# CircleValve.net
KiCad netlist of a schematic drawn in Altium Designer
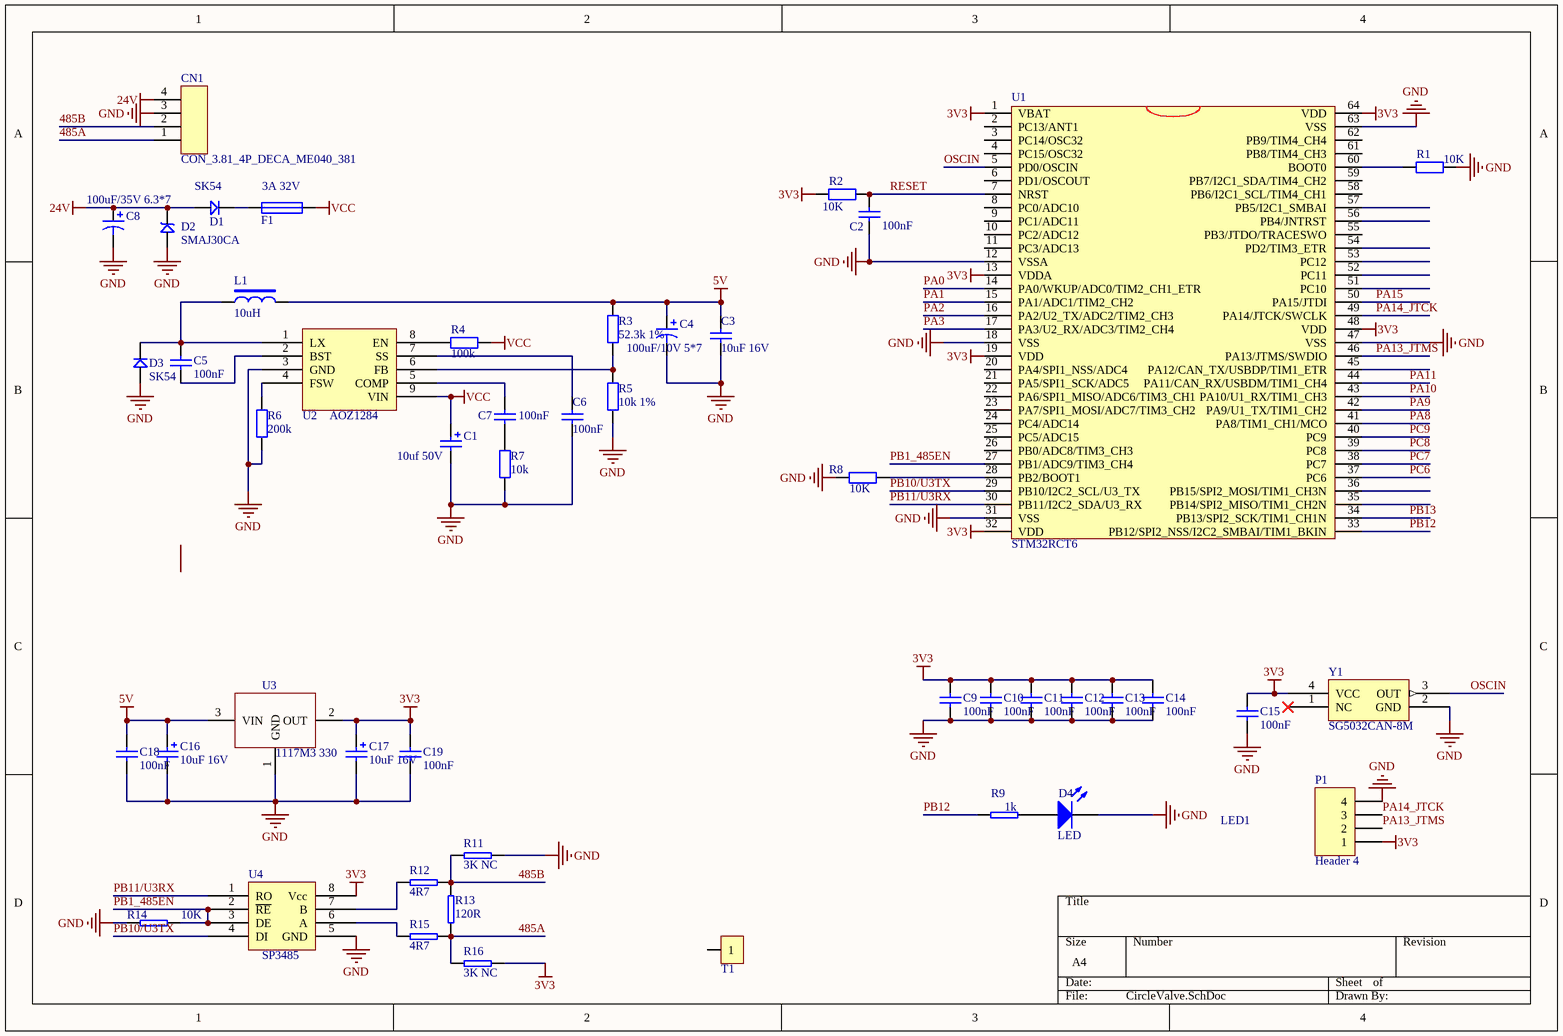
[diagram p0: CircleValve.SchDoc]

(export (version "E")
  (design (tool "Eeschema 10.0.6"))
  (components
    (comp (ref "C1") (value "10uf 50V") (footprint "C1206") (libsource (lib "stm32_s") (part "CAP1")))
    (comp (ref "C2") (value "100nF") (footprint "C0603") (libsource (lib "stm32_s") (part "CAP")))
    (comp (ref "C3") (value "10uF 16V") (footprint "C1206") (libsource (lib "stm32_s") (part "CAP")))
    (comp (ref "C4")
      (value "100uF/10V 5*7")
      (footprint "CAP D=6mm")
      (description "Polarized Capacitor (Radial)")
      (fields (field (name "PUBLISHER") "Altium Limited"))
      (libsource (lib "Skcl") (part "Cap Pol1"))
    )
    (comp (ref "C5") (value "100nF") (footprint "C0603") (libsource (lib "stm32_s") (part "CAP")))
    (comp (ref "C6") (value "100nF") (footprint "C0603") (libsource (lib "stm32_s") (part "CAP")))
    (comp (ref "C7") (value "100nF") (footprint "C0603") (libsource (lib "stm32_s") (part "CAP")))
    (comp (ref "C8")
      (value "100uF/35V 6.3*7")
      (footprint "CAP D=6mm")
      (description "Polarized Capacitor (Radial)")
      (fields (field (name "PUBLISHER") "Altium Limited"))
      (libsource (lib "Skcl") (part "Cap Pol1"))
    )
    (comp (ref "C9") (value "100nF") (footprint "C0603") (libsource (lib "stm32_s") (part "CAP")))
    (comp (ref "C10") (value "100nF") (footprint "C0603") (libsource (lib "stm32_s") (part "CAP")))
    (comp (ref "C11") (value "100nF") (footprint "C0603") (libsource (lib "stm32_s") (part "CAP")))
    (comp (ref "C12") (value "100nF") (footprint "C0603") (libsource (lib "stm32_s") (part "CAP")))
    (comp (ref "C13") (value "100nF") (footprint "C0603") (libsource (lib "stm32_s") (part "CAP")))
    (comp (ref "C14") (value "100nF") (footprint "C0603") (libsource (lib "stm32_s") (part "CAP")))
    (comp (ref "C15") (value "100nF") (footprint "C0603") (libsource (lib "stm32_s") (part "CAP")))
    (comp (ref "C16") (value "10uF 16V") (footprint "C1206") (libsource (lib "stm32_s") (part "CAP1")))
    (comp (ref "C17") (value "10uF 16V") (footprint "C1206") (libsource (lib "stm32_s") (part "CAP1")))
    (comp (ref "C18") (value "100nF") (footprint "C0603") (libsource (lib "stm32_s") (part "CAP")))
    (comp (ref "C19") (value "100nF") (footprint "C0603") (libsource (lib "stm32_s") (part "CAP")))
    (comp (ref "CN1")
      (value "CON_3.81_4P_DECA_ME040_381")
      (footprint "ME040_381_4P_VC-1")
      (description "DECA connector,3.81mm,1*4P,180度")
      (fields (field (name "MANUFACTURER") "DECA") (field (name "PARTNUMBER") "ME040-381-4P"))
      (libsource (lib "Schlib1") (part "CON_3.81_4P_DECA_ME040_381"))
    )
    (comp (ref "D1")
      (value "SK54")
      (footprint "LC-SMA(DO-214AC)_S3")
      (description "1N4148")
      (libsource (lib "stm32_s") (part "D"))
    )
    (comp (ref "D2")
      (value "SMAJ30CA")
      (footprint "LC-SMA(DO-214AC)_S3")
      (description "TVS")
      (libsource (lib "stm32_s") (part "SMBJ"))
    )
    (comp (ref "D3")
      (value "SK54")
      (footprint "LC-SMA(DO-214AC)_S3")
      (description "1N4148")
      (libsource (lib "stm32_s") (part "D"))
    )
    (comp (ref "D4") (value "LED") (footprint "LED_M") (libsource (lib "stm32_s") (part "LED")))
    (comp (ref "F1") (value "3A 32V") (footprint "C1206") (libsource (lib "库") (part "FUSE")))
    (comp (ref "L1") (value "10uH") (footprint "L_SOP74") (libsource (lib "库") (part "差模电感")))
    (comp (ref "P1")
      (value "Header 4")
      (footprint "Header4-2.54mm")
      (description "Header, 4-Pin")
      (fields (field (name "PUBLISHER") "Altium Limited"))
      (libsource (lib "Miscellaneous Connectors") (part "Header 4"))
    )
    (comp (ref "R1") (value "10K") (footprint "R0603") (libsource (lib "stm32") (part "RES")))
    (comp (ref "R2") (value "10K") (footprint "R0603") (libsource (lib "") (part "RES_1")))
    (comp (ref "R3") (value "52.3k 1%") (footprint "R0603") (libsource (lib "stm32_s") (part "RES")))
    (comp (ref "R4") (value "100k") (footprint "R0603") (libsource (lib "") (part "RES_1")))
    (comp (ref "R5") (value "10k 1%") (footprint "R0603") (libsource (lib "stm32_s") (part "RES")))
    (comp (ref "R6") (value "200k") (footprint "R0603") (libsource (lib "stm32_s") (part "RES")))
    (comp (ref "R7") (value "10k") (footprint "R0603") (libsource (lib "stm32_s") (part "RES")))
    (comp (ref "R8") (value "10K") (footprint "R0603") (libsource (lib "stm32") (part "RES")))
    (comp (ref "R9")
      (value "1k")
      (footprint "R0603")
      (description "标贴电阻")
      (libsource (lib "stm32_s") (part "R"))
    )
    (comp (ref "R11")
      (value "3K NC")
      (footprint "R0603")
      (description "标贴电阻")
      (libsource (lib "stm32_s") (part "R"))
    )
    (comp (ref "R12")
      (value "4R7")
      (footprint "R0603")
      (description "标贴电阻")
      (libsource (lib "stm32_s") (part "R"))
    )
    (comp (ref "R13")
      (value "120R")
      (footprint "R0603")
      (description "标贴电阻")
      (libsource (lib "stm32_s") (part "R"))
    )
    (comp (ref "R14")
      (value "10K")
      (footprint "R0603")
      (description "标贴电阻")
      (libsource (lib "stm32_s") (part "R"))
    )
    (comp (ref "R15")
      (value "4R7")
      (footprint "R0603")
      (description "标贴电阻")
      (libsource (lib "stm32_s") (part "R"))
    )
    (comp (ref "R16")
      (value "3K NC")
      (footprint "R0603")
      (description "标贴电阻")
      (libsource (lib "stm32_s") (part "R"))
    )
    (comp (ref "T1") (value "TP") (footprint "定位孔3mm") (libsource (lib "stm32_s") (part "TP")))
    (comp (ref "U1")
      (value "STM32RCT6")
      (footprint "LC-LQFP-64_10x10x05P")
      (libsource (lib "stm32") (part "STM32RBT6"))
    )
    (comp (ref "U2") (value "AOZ1284") (footprint "LC-SOP-8_150mil") (libsource (lib "库") (part "AOZ1284")))
    (comp (ref "U3") (value "1117M3 330") (footprint "LT1117") (libsource (lib "stm32_s") (part "LT1117")))
    (comp (ref "U4") (value "SP3485") (footprint "SO8") (libsource (lib "stm32_s") (part "RS485")))
    (comp (ref "Y1")
      (value "SG5032CAN-8M")
      (footprint "XTAL-4P-5*3MM")
      (libsource (lib "Freq") (part "XTAL_POWER"))
    )
  )
  (nets
    (net (code "1") (name "/485A") (class "Default")
      (node (ref "CN1") (pin "1") (pinfunction "1_1") (pintype "passive"))
      (node (ref "R13") (pin "2") (pinfunction "2_2") (pintype "passive"))
      (node (ref "R15") (pin "1") (pinfunction "1_1") (pintype "passive"))
      (node (ref "R16") (pin "2") (pinfunction "2_2") (pintype "passive"))
    )
    (net (code "2") (name "/485B") (class "Default")
      (node (ref "CN1") (pin "2") (pinfunction "2_2") (pintype "passive"))
      (node (ref "R11") (pin "2") (pinfunction "2_2") (pintype "passive"))
      (node (ref "R12") (pin "1") (pinfunction "1_1") (pintype "passive"))
      (node (ref "R13") (pin "1") (pinfunction "1_1") (pintype "passive"))
    )
    (net (code "3") (name "/OSCIN") (class "Default")
      (node (ref "U1") (pin "5") (pinfunction "PD0/OSCIN_5") (pintype "passive"))
      (node (ref "Y1") (pin "3") (pinfunction "OUT_3") (pintype "output"))
    )
    (net (code "4") (name "/PA0") (class "Default")
      (node (ref "U1") (pin "14") (pinfunction "PA0/WKUP/ADC0/TIM2_CH1_ETR_14") (pintype "passive"))
    )
    (net (code "5") (name "/PA1") (class "Default")
      (node (ref "U1") (pin "15") (pinfunction "PA1/ADC1/TIM2_CH2_15") (pintype "passive"))
    )
    (net (code "6") (name "/PA2") (class "Default")
      (node (ref "U1") (pin "16") (pinfunction "PA2/U2_TX/ADC2/TIM2_CH3_16") (pintype "passive"))
    )
    (net (code "7") (name "/PA3") (class "Default")
      (node (ref "U1") (pin "17") (pinfunction "PA3/U2_RX/ADC3/TIM2_CH4_17") (pintype "passive"))
    )
    (net (code "8") (name "/PA8") (class "Default")
      (node (ref "U1") (pin "41") (pinfunction "PA8/TIM1_CH1/MCO_41") (pintype "passive"))
    )
    (net (code "9") (name "/PA9") (class "Default")
      (node (ref "U1") (pin "42") (pinfunction "PA9/U1_TX/TIM1_CH2_42") (pintype "passive"))
    )
    (net (code "10") (name "/PA10") (class "Default")
      (node (ref "U1") (pin "43") (pinfunction "PA10/U1_RX/TIM1_CH3_43") (pintype "passive"))
    )
    (net (code "11") (name "/PA11") (class "Default")
      (node (ref "U1") (pin "44") (pinfunction "PA11/CAN_RX/USBDM/TIM1_CH4_44") (pintype "passive"))
    )
    (net (code "12") (name "/PA13_JTMS") (class "Default")
      (node (ref "P1") (pin "2") (pinfunction "2_2") (pintype "passive"))
      (node (ref "U1") (pin "46") (pinfunction "PA13/JTMS/SWDIO_46") (pintype "passive"))
    )
    (net (code "13") (name "/PA14_JTCK") (class "Default")
      (node (ref "P1") (pin "3") (pinfunction "3_3") (pintype "passive"))
      (node (ref "U1") (pin "49") (pinfunction "PA14/JTCK/SWCLK_49") (pintype "passive"))
    )
    (net (code "14") (name "/PA15") (class "Default")
      (node (ref "U1") (pin "50") (pinfunction "PA15/JTDI_50") (pintype "passive"))
    )
    (net (code "15") (name "/PB1_485EN") (class "Default")
      (node (ref "R14") (pin "2") (pinfunction "2_2") (pintype "passive"))
      (node (ref "U1") (pin "27") (pinfunction "PB1/ADC9/TIM3_CH4_27") (pintype "passive"))
      (node (ref "U4") (pin "2") (pinfunction "~{RE}_2") (pintype "passive"))
      (node (ref "U4") (pin "3") (pinfunction "DE_3") (pintype "passive"))
    )
    (net (code "16") (name "/PB10{slash}U3TX") (class "Default")
      (node (ref "U1") (pin "29") (pinfunction "PB10/I2C2_SCL/U3_TX_29") (pintype "passive"))
      (node (ref "U4") (pin "4") (pinfunction "DI_4") (pintype "passive"))
    )
    (net (code "17") (name "/PB11{slash}U3RX") (class "Default")
      (node (ref "U1") (pin "30") (pinfunction "PB11/I2C2_SDA/U3_RX_30") (pintype "passive"))
      (node (ref "U4") (pin "1") (pinfunction "RO_1") (pintype "passive"))
    )
    (net (code "18") (name "/PB12") (class "Default")
      (node (ref "R9") (pin "1") (pinfunction "1_1") (pintype "passive"))
      (node (ref "U1") (pin "33") (pinfunction "PB12/SPI2_NSS/I2C2_SMBAI/TIM1_BKIN_33") (pintype "passive"))
    )
    (net (code "19") (name "/PB13") (class "Default")
      (node (ref "U1") (pin "34") (pinfunction "PB13/SPI2_SCK/TIM1_CH1N_34") (pintype "passive"))
    )
    (net (code "20") (name "/PC6") (class "Default")
      (node (ref "U1") (pin "37") (pinfunction "PC6_37") (pintype "passive"))
    )
    (net (code "21") (name "/PC7") (class "Default")
      (node (ref "U1") (pin "38") (pinfunction "PC7_38") (pintype "passive"))
    )
    (net (code "22") (name "/PC8") (class "Default")
      (node (ref "U1") (pin "39") (pinfunction "PC8_39") (pintype "passive"))
    )
    (net (code "23") (name "/PC9") (class "Default")
      (node (ref "U1") (pin "40") (pinfunction "PC9_40") (pintype "passive"))
    )
    (net (code "24") (name "/RESET") (class "Default")
      (node (ref "C2") (pin "1") (pinfunction "1_1") (pintype "passive"))
      (node (ref "R2") (pin "2") (pinfunction "2_2") (pintype "passive"))
      (node (ref "U1") (pin "7") (pinfunction "NRST_7") (pintype "passive"))
    )
    (net (code "25") (name "3V3") (class "Default")
      (node (ref "C10") (pin "2") (pinfunction "2_2") (pintype "passive"))
      (node (ref "C11") (pin "2") (pinfunction "2_2") (pintype "passive"))
      (node (ref "C12") (pin "2") (pinfunction "2_2") (pintype "passive"))
      (node (ref "C13") (pin "2") (pinfunction "2_2") (pintype "passive"))
      (node (ref "C14") (pin "2") (pinfunction "2_2") (pintype "passive"))
      (node (ref "C15") (pin "2") (pinfunction "2_2") (pintype "passive"))
      (node (ref "C17") (pin "1") (pinfunction "1_1") (pintype "passive"))
      (node (ref "C19") (pin "2") (pinfunction "2_2") (pintype "passive"))
      (node (ref "C9") (pin "2") (pinfunction "2_2") (pintype "passive"))
      (node (ref "P1") (pin "1") (pinfunction "1_1") (pintype "passive"))
      (node (ref "R16") (pin "1") (pinfunction "1_1") (pintype "passive"))
      (node (ref "R2") (pin "1") (pinfunction "1_1") (pintype "passive"))
      (node (ref "U1") (pin "1") (pinfunction "VBAT_1") (pintype "passive"))
      (node (ref "U1") (pin "13") (pinfunction "VDDA_13") (pintype "passive"))
      (node (ref "U1") (pin "19") (pinfunction "VDD_19") (pintype "passive"))
      (node (ref "U1") (pin "32") (pinfunction "VDD_32") (pintype "passive"))
      (node (ref "U1") (pin "48") (pinfunction "VDD_48") (pintype "passive"))
      (node (ref "U1") (pin "64") (pinfunction "VDD_64") (pintype "passive"))
      (node (ref "U3") (pin "2") (pinfunction "OUT_2") (pintype "passive"))
      (node (ref "U4") (pin "8") (pinfunction "Vcc_8") (pintype "passive"))
      (node (ref "Y1") (pin "4") (pinfunction "VCC_4") (pintype "passive"))
    )
    (net (code "26") (name "5V") (class "Default")
      (node (ref "C16") (pin "1") (pinfunction "1_1") (pintype "passive"))
      (node (ref "C18") (pin "2") (pinfunction "2_2") (pintype "passive"))
      (node (ref "C3") (pin "1") (pinfunction "1_1") (pintype "passive"))
      (node (ref "C4") (pin "1") (pinfunction "1_1") (pintype "passive"))
      (node (ref "L1") (pin "2") (pinfunction "2_2") (pintype "passive"))
      (node (ref "R3") (pin "2") (pinfunction "2_2") (pintype "passive"))
      (node (ref "U3") (pin "3") (pinfunction "VIN_3") (pintype "passive"))
    )
    (net (code "27") (name "24V") (class "Default")
      (node (ref "C8") (pin "1") (pinfunction "1_1") (pintype "passive"))
      (node (ref "CN1") (pin "4") (pinfunction "4_4") (pintype "passive"))
      (node (ref "D1") (pin "1") (pintype "passive"))
      (node (ref "D2") (pin "2") (pintype "passive"))
    )
    (net (code "28") (name "GND") (class "Default")
      (node (ref "C1") (pin "2") (pinfunction "2_2") (pintype "passive"))
      (node (ref "C10") (pin "1") (pinfunction "1_1") (pintype "passive"))
      (node (ref "C11") (pin "1") (pinfunction "1_1") (pintype "passive"))
      (node (ref "C12") (pin "1") (pinfunction "1_1") (pintype "passive"))
      (node (ref "C13") (pin "1") (pinfunction "1_1") (pintype "passive"))
      (node (ref "C14") (pin "1") (pinfunction "1_1") (pintype "passive"))
      (node (ref "C15") (pin "1") (pinfunction "1_1") (pintype "passive"))
      (node (ref "C16") (pin "2") (pinfunction "2_2") (pintype "passive"))
      (node (ref "C17") (pin "2") (pinfunction "2_2") (pintype "passive"))
      (node (ref "C18") (pin "1") (pinfunction "1_1") (pintype "passive"))
      (node (ref "C19") (pin "1") (pinfunction "1_1") (pintype "passive"))
      (node (ref "C2") (pin "2") (pinfunction "2_2") (pintype "passive"))
      (node (ref "C3") (pin "2") (pinfunction "2_2") (pintype "passive"))
      (node (ref "C4") (pin "2") (pinfunction "2_2") (pintype "passive"))
      (node (ref "C6") (pin "2") (pinfunction "2_2") (pintype "passive"))
      (node (ref "C8") (pin "2") (pinfunction "2_2") (pintype "passive"))
      (node (ref "C9") (pin "1") (pinfunction "1_1") (pintype "passive"))
      (node (ref "CN1") (pin "3") (pinfunction "3_3") (pintype "passive"))
      (node (ref "D2") (pin "1") (pintype "passive"))
      (node (ref "D3") (pin "1") (pintype "passive"))
      (node (ref "D4") (pin "2") (pinfunction "K_2") (pintype "passive"))
      (node (ref "P1") (pin "4") (pinfunction "4_4") (pintype "passive"))
      (node (ref "R1") (pin "2") (pinfunction "2_2") (pintype "passive"))
      (node (ref "R11") (pin "1") (pinfunction "1_1") (pintype "passive"))
      (node (ref "R14") (pin "1") (pinfunction "1_1") (pintype "passive"))
      (node (ref "R5") (pin "1") (pinfunction "1_1") (pintype "passive"))
      (node (ref "R6") (pin "1") (pinfunction "1_1") (pintype "passive"))
      (node (ref "R7") (pin "1") (pinfunction "1_1") (pintype "passive"))
      (node (ref "R8") (pin "1") (pinfunction "1_1") (pintype "passive"))
      (node (ref "U1") (pin "12") (pinfunction "VSSA_12") (pintype "passive"))
      (node (ref "U1") (pin "18") (pinfunction "VSS_18") (pintype "passive"))
      (node (ref "U1") (pin "31") (pinfunction "VSS_31") (pintype "passive"))
      (node (ref "U1") (pin "47") (pinfunction "VSS_47") (pintype "passive"))
      (node (ref "U1") (pin "63") (pinfunction "VSS_63") (pintype "passive"))
      (node (ref "U2") (pin "3") (pinfunction "GND_3") (pintype "passive"))
      (node (ref "U3") (pin "1") (pinfunction "GND_1") (pintype "passive"))
      (node (ref "U4") (pin "5") (pinfunction "GND_5") (pintype "passive"))
      (node (ref "Y1") (pin "2") (pinfunction "GND_2") (pintype "passive"))
    )
    (net (code "29") (name "Net-(C7-Pad2)") (class "Default")
      (node (ref "C7") (pin "2") (pinfunction "2_2") (pintype "passive"))
      (node (ref "R7") (pin "2") (pinfunction "2_2") (pintype "passive"))
    )
    (net (code "30") (name "Net-(D1-Pad2)") (class "Default")
      (node (ref "D1") (pin "2") (pintype "passive"))
      (node (ref "F1") (pin "1") (pinfunction "1_1") (pintype "passive"))
    )
    (net (code "31") (name "Net-(D4-A)") (class "Default")
      (node (ref "D4") (pin "1") (pinfunction "A_1") (pintype "passive"))
      (node (ref "R9") (pin "2") (pinfunction "2_2") (pintype "passive"))
    )
    (net (code "32") (name "Net-(U1-BOOT0)") (class "Default")
      (node (ref "R1") (pin "1") (pinfunction "1_1") (pintype "passive"))
      (node (ref "U1") (pin "60") (pinfunction "BOOT0_60") (pintype "passive"))
    )
    (net (code "33") (name "Net-(U1-PB2{slash}BOOT1)") (class "Default")
      (node (ref "R8") (pin "2") (pinfunction "2_2") (pintype "passive"))
      (node (ref "U1") (pin "28") (pinfunction "PB2/BOOT1_28") (pintype "passive"))
    )
    (net (code "34") (name "Net-(U2-BST)") (class "Default")
      (node (ref "C5") (pin "1") (pinfunction "1_1") (pintype "passive"))
      (node (ref "U2") (pin "2") (pinfunction "BST_2") (pintype "passive"))
    )
    (net (code "35") (name "Net-(U2-COMP)") (class "Default")
      (node (ref "C7") (pin "1") (pinfunction "1_1") (pintype "passive"))
      (node (ref "U2") (pin "5") (pinfunction "COMP_5") (pintype "passive"))
    )
    (net (code "36") (name "Net-(U2-EN)") (class "Default")
      (node (ref "R4") (pin "1") (pinfunction "1_1") (pintype "passive"))
      (node (ref "U2") (pin "8") (pinfunction "EN_8") (pintype "passive"))
    )
    (net (code "37") (name "Net-(U2-FB)") (class "Default")
      (node (ref "R3") (pin "1") (pinfunction "1_1") (pintype "passive"))
      (node (ref "R5") (pin "2") (pinfunction "2_2") (pintype "passive"))
      (node (ref "U2") (pin "6") (pinfunction "FB_6") (pintype "passive"))
    )
    (net (code "38") (name "Net-(U2-FSW)") (class "Default")
      (node (ref "R6") (pin "2") (pinfunction "2_2") (pintype "passive"))
      (node (ref "U2") (pin "4") (pinfunction "FSW_4") (pintype "passive"))
    )
    (net (code "39") (name "Net-(U2-LX)") (class "Default")
      (node (ref "C5") (pin "2") (pinfunction "2_2") (pintype "passive"))
      (node (ref "D3") (pin "2") (pintype "passive"))
      (node (ref "L1") (pin "1") (pinfunction "1_1") (pintype "passive"))
      (node (ref "U2") (pin "1") (pinfunction "LX_1") (pintype "passive"))
    )
    (net (code "40") (name "Net-(U2-SS)") (class "Default")
      (node (ref "C6") (pin "1") (pinfunction "1_1") (pintype "passive"))
      (node (ref "U2") (pin "7") (pinfunction "SS_7") (pintype "passive"))
    )
    (net (code "41") (name "Net-(U4-A)") (class "Default")
      (node (ref "R15") (pin "2") (pinfunction "2_2") (pintype "passive"))
      (node (ref "U4") (pin "6") (pinfunction "A_6") (pintype "passive"))
    )
    (net (code "42") (name "Net-(U4-B)") (class "Default")
      (node (ref "R12") (pin "2") (pinfunction "2_2") (pintype "passive"))
      (node (ref "U4") (pin "7") (pinfunction "B_7") (pintype "passive"))
    )
    (net (code "43") (name "VCC") (class "Default")
      (node (ref "C1") (pin "1") (pinfunction "1_1") (pintype "passive"))
      (node (ref "F1") (pin "2") (pinfunction "2_2") (pintype "passive"))
      (node (ref "R4") (pin "2") (pinfunction "2_2") (pintype "passive"))
      (node (ref "U2") (pin "9") (pinfunction "VIN_9") (pintype "passive"))
    )
    (net (code "44") (name "unconnected-(T1-Pad1)") (class "Default")
      (node (ref "T1") (pin "1") (pinfunction "1_1") (pintype "passive"))
    )
    (net (code "45") (name "unconnected-(U1-PA4{slash}SPI1_NSS{slash}ADC4-Pad20)") (class "Default")
      (node (ref "U1") (pin "20") (pinfunction "PA4/SPI1_NSS/ADC4_20") (pintype "passive"))
    )
    (net (code "46") (name "unconnected-(U1-PA5{slash}SPI1_SCK{slash}ADC5-Pad21)") (class "Default")
      (node (ref "U1") (pin "21") (pinfunction "PA5/SPI1_SCK/ADC5_21") (pintype "passive"))
    )
    (net (code "47") (name "unconnected-(U1-PA6{slash}SPI1_MISO{slash}ADC6{slash}TIM3_CH1-Pad22)") (class "Default")
      (node (ref "U1") (pin "22") (pinfunction "PA6/SPI1_MISO/ADC6/TIM3_CH1_22") (pintype "passive"))
    )
    (net (code "48") (name "unconnected-(U1-PA7{slash}SPI1_MOSI{slash}ADC7{slash}TIM3_CH2-Pad23)") (class "Default")
      (node (ref "U1") (pin "23") (pinfunction "PA7/SPI1_MOSI/ADC7/TIM3_CH2_23") (pintype "passive"))
    )
    (net (code "49") (name "unconnected-(U1-PA12{slash}CAN_TX{slash}USBDP{slash}TIM1_ETR-Pad45)") (class "Default")
      (node (ref "U1") (pin "45") (pinfunction "PA12/CAN_TX/USBDP/TIM1_ETR_45") (pintype "passive"))
    )
    (net (code "50") (name "unconnected-(U1-PB0{slash}ADC8{slash}TIM3_CH3-Pad26)") (class "Default")
      (node (ref "U1") (pin "26") (pinfunction "PB0/ADC8/TIM3_CH3_26") (pintype "passive"))
    )
    (net (code "51") (name "unconnected-(U1-PB3{slash}JTDO{slash}TRACESWO-Pad55)") (class "Default")
      (node (ref "U1") (pin "55") (pinfunction "PB3/JTDO/TRACESWO_55") (pintype "passive"))
    )
    (net (code "52") (name "unconnected-(U1-PB4{slash}JNTRST-Pad56)") (class "Default")
      (node (ref "U1") (pin "56") (pinfunction "PB4/JNTRST_56") (pintype "passive"))
    )
    (net (code "53") (name "unconnected-(U1-PB5{slash}I2C1_SMBAI-Pad57)") (class "Default")
      (node (ref "U1") (pin "57") (pinfunction "PB5/I2C1_SMBAI_57") (pintype "passive"))
    )
    (net (code "54") (name "unconnected-(U1-PB6{slash}I2C1_SCL{slash}TIM4_CH1-Pad58)") (class "Default")
      (node (ref "U1") (pin "58") (pinfunction "PB6/I2C1_SCL/TIM4_CH1_58") (pintype "passive"))
    )
    (net (code "55") (name "unconnected-(U1-PB7{slash}I2C1_SDA{slash}TIM4_CH2-Pad59)") (class "Default")
      (node (ref "U1") (pin "59") (pinfunction "PB7/I2C1_SDA/TIM4_CH2_59") (pintype "passive"))
    )
    (net (code "56") (name "unconnected-(U1-PB8{slash}TIM4_CH3-Pad61)") (class "Default")
      (node (ref "U1") (pin "61") (pinfunction "PB8/TIM4_CH3_61") (pintype "passive"))
    )
    (net (code "57") (name "unconnected-(U1-PB9{slash}TIM4_CH4-Pad62)") (class "Default")
      (node (ref "U1") (pin "62") (pinfunction "PB9/TIM4_CH4_62") (pintype "passive"))
    )
    (net (code "58") (name "unconnected-(U1-PB14{slash}SPI2_MISO{slash}TIM1_CH2N-Pad35)") (class "Default")
      (node (ref "U1") (pin "35") (pinfunction "PB14/SPI2_MISO/TIM1_CH2N_35") (pintype "passive"))
    )
    (net (code "59") (name "unconnected-(U1-PB15{slash}SPI2_MOSI{slash}TIM1_CH3N-Pad36)") (class "Default")
      (node (ref "U1") (pin "36") (pinfunction "PB15/SPI2_MOSI/TIM1_CH3N_36") (pintype "passive"))
    )
    (net (code "60") (name "unconnected-(U1-PC0{slash}ADC10-Pad8)") (class "Default")
      (node (ref "U1") (pin "8") (pinfunction "PC0/ADC10_8") (pintype "passive"))
    )
    (net (code "61") (name "unconnected-(U1-PC1{slash}ADC11-Pad9)") (class "Default")
      (node (ref "U1") (pin "9") (pinfunction "PC1/ADC11_9") (pintype "passive"))
    )
    (net (code "62") (name "unconnected-(U1-PC2{slash}ADC12-Pad10)") (class "Default")
      (node (ref "U1") (pin "10") (pinfunction "PC2/ADC12_10") (pintype "passive"))
    )
    (net (code "63") (name "unconnected-(U1-PC3{slash}ADC13-Pad11)") (class "Default")
      (node (ref "U1") (pin "11") (pinfunction "PC3/ADC13_11") (pintype "passive"))
    )
    (net (code "64") (name "unconnected-(U1-PC4{slash}ADC14-Pad24)") (class "Default")
      (node (ref "U1") (pin "24") (pinfunction "PC4/ADC14_24") (pintype "passive"))
    )
    (net (code "65") (name "unconnected-(U1-PC5{slash}ADC15-Pad25)") (class "Default")
      (node (ref "U1") (pin "25") (pinfunction "PC5/ADC15_25") (pintype "passive"))
    )
    (net (code "66") (name "unconnected-(U1-PC10-Pad51)") (class "Default")
      (node (ref "U1") (pin "51") (pinfunction "PC10_51") (pintype "passive"))
    )
    (net (code "67") (name "unconnected-(U1-PC11-Pad52)") (class "Default")
      (node (ref "U1") (pin "52") (pinfunction "PC11_52") (pintype "passive"))
    )
    (net (code "68") (name "unconnected-(U1-PC12-Pad53)") (class "Default")
      (node (ref "U1") (pin "53") (pinfunction "PC12_53") (pintype "passive"))
    )
    (net (code "69") (name "unconnected-(U1-PC13{slash}ANT1-Pad2)") (class "Default")
      (node (ref "U1") (pin "2") (pinfunction "PC13/ANT1_2") (pintype "passive"))
    )
    (net (code "70") (name "unconnected-(U1-PC14{slash}OSC32-Pad3)") (class "Default")
      (node (ref "U1") (pin "3") (pinfunction "PC14/OSC32_3") (pintype "passive"))
    )
    (net (code "71") (name "unconnected-(U1-PC15{slash}OSC32-Pad4)") (class "Default")
      (node (ref "U1") (pin "4") (pinfunction "PC15/OSC32_4") (pintype "passive"))
    )
    (net (code "72") (name "unconnected-(U1-PD1{slash}OSCOUT-Pad6)") (class "Default")
      (node (ref "U1") (pin "6") (pinfunction "PD1/OSCOUT_6") (pintype "passive"))
    )
    (net (code "73") (name "unconnected-(U1-PD2{slash}TIM3_ETR-Pad54)") (class "Default")
      (node (ref "U1") (pin "54") (pinfunction "PD2/TIM3_ETR_54") (pintype "passive"))
    )
    (net (code "74") (name "unconnected-(Y1-NC-Pad1)") (class "Default")
      (node (ref "Y1") (pin "1") (pinfunction "NC_1") (pintype "passive+no_connect"))
    )
  )
)
